# MJE13001_SWITCHING_NO_FEEDBACK.net
KiCad netlist of a schematic drawn in Altium Designer
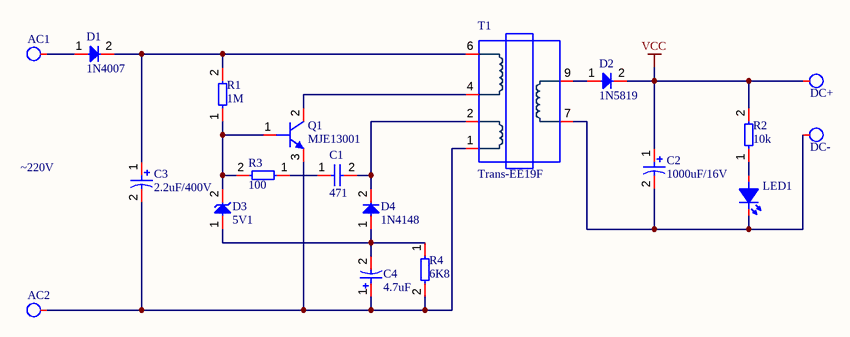
[diagram p0: MJE13001_SWITCHING_NO_FEEDBACK.SchDoc]

(export (version "E")
  (design (tool "Eeschema 10.0.6"))
  (components
    (comp (ref "AC1")
      (value "SolderPoint")
      (footprint "SolderPoint")
      (libsource (lib "Lib31082020") (part "SolderPoint"))
    )
    (comp (ref "AC2")
      (value "SolderPoint")
      (footprint "SolderPoint")
      (libsource (lib "Lib31082020") (part "SolderPoint"))
    )
    (comp (ref "C1")
      (value "471")
      (footprint "CAP_DISC_PITCH_2.54MM")
      (libsource (lib "Lib31082020") (part "Capacitors(Disc)"))
    )
    (comp (ref "C2")
      (value "1000uF/16V")
      (footprint "CAP_RAD_7mm")
      (libsource (lib "Lib31082020") (part "Capacitor(Radian)"))
    )
    (comp (ref "C3")
      (value "2.2uF/400V")
      (footprint "CAP_RAD_7mm")
      (libsource (lib "Lib31082020") (part "Capacitor(Radian)"))
    )
    (comp (ref "C4")
      (value "4.7uF")
      (footprint "CAP_RAD_4mm")
      (libsource (lib "Lib31082020") (part "Capacitor(Radian)"))
    )
    (comp (ref "D1") (value "1N4007") (footprint "DO-41") (libsource (lib "Lib31082020") (part "1N4007")))
    (comp (ref "D2")
      (value "1N5819")
      (footprint "DO-35 Horizontal")
      (libsource (lib "Lib31082020") (part "Diode 1N4148"))
    )
    (comp (ref "D3")
      (value "5V1")
      (footprint "DO-35 Horizontal")
      (libsource (lib "Lib31082020") (part "Diode Zener"))
    )
    (comp (ref "D4")
      (value "1N4148")
      (footprint "DO-35 Horizontal")
      (libsource (lib "Lib31082020") (part "Diode 1N4148"))
    )
    (comp (ref "DC+")
      (value "SolderPoint")
      (footprint "SolderPoint")
      (libsource (lib "Lib31082020") (part "SolderPoint"))
    )
    (comp (ref "DC-")
      (value "SolderPoint")
      (footprint "SolderPoint")
      (libsource (lib "Lib31082020") (part "SolderPoint"))
    )
    (comp (ref "LED1")
      (value "LED 5mm")
      (footprint "LED_5MM")
      (libsource (lib "Lib31082020") (part "LED 5mm"))
    )
    (comp (ref "Q1")
      (value "MJE13001")
      (footprint "TO-92")
      (libsource (lib "Lib31082020") (part "MJE13001_Type_F"))
    )
    (comp (ref "R1") (value "1M") (footprint "RES-0.25W-H-MF") (libsource (lib "") (part "Resistors THD_2")))
    (comp (ref "R2") (value "10k") (footprint "R0805") (libsource (lib "Lib31082020") (part "Resistor SMD")))
    (comp (ref "R3") (value "100") (footprint "RES-0.25W-H-MF") (libsource (lib "") (part "Resistors THD_1")))
    (comp (ref "R4")
      (value "6K8")
      (footprint "RES-0.25W-H-MF")
      (libsource (lib "Lib31082020") (part "Resistors THD"))
    )
    (comp (ref "T1")
      (value "Trans-EE19F")
      (footprint "TRANS_EE19F")
      (libsource (lib "Lib31082020") (part "Trans-EE19F"))
    )
  )
  (nets
    (net (code "1") (name "Net-(AC1-Pad1)") (class "Default")
      (node (ref "AC1") (pin "1") (pinfunction "1_1") (pintype "passive"))
      (node (ref "D1") (pin "1") (pinfunction "1_1") (pintype "passive"))
    )
    (net (code "2") (name "Net-(C1-Pad1)") (class "Default")
      (node (ref "C1") (pin "1") (pinfunction "1_1") (pintype "passive"))
      (node (ref "R3") (pin "1") (pinfunction "1_1") (pintype "passive"))
    )
    (net (code "3") (name "Net-(C1-Pad2)") (class "Default")
      (node (ref "C1") (pin "2") (pinfunction "2_2") (pintype "passive"))
      (node (ref "D4") (pin "2") (pinfunction "2_2") (pintype "passive"))
      (node (ref "T1") (pin "2") (pinfunction "2_2") (pintype "passive"))
    )
    (net (code "4") (name "Net-(C4-Pad2)") (class "Default")
      (node (ref "C4") (pin "2") (pinfunction "2_2") (pintype "passive"))
      (node (ref "D3") (pin "1") (pinfunction "1_1") (pintype "passive"))
      (node (ref "D4") (pin "1") (pinfunction "1_1") (pintype "passive"))
      (node (ref "R4") (pin "1") (pinfunction "1_1") (pintype "passive"))
    )
    (net (code "5") (name "Net-(D2-Pad1)") (class "Default")
      (node (ref "D2") (pin "1") (pinfunction "1_1") (pintype "passive"))
      (node (ref "T1") (pin "9") (pinfunction "9_9") (pintype "passive"))
    )
    (net (code "6") (name "Net-(LED1-A)") (class "Default")
      (node (ref "LED1") (pin "1") (pinfunction "A_1") (pintype "passive"))
      (node (ref "R2") (pin "1") (pinfunction "1_1") (pintype "passive"))
    )
    (net (code "7") (name "Net-(LED1-K)") (class "Default")
      (node (ref "C2") (pin "2") (pinfunction "2_2") (pintype "passive"))
      (node (ref "DC-") (pin "1") (pinfunction "1_1") (pintype "passive"))
      (node (ref "LED1") (pin "2") (pinfunction "K_2") (pintype "passive"))
      (node (ref "T1") (pin "7") (pinfunction "7_7") (pintype "passive"))
    )
    (net (code "8") (name "Net-(Q1-B)") (class "Default")
      (node (ref "D3") (pin "2") (pinfunction "2_2") (pintype "passive"))
      (node (ref "Q1") (pin "1") (pinfunction "B_1") (pintype "passive"))
      (node (ref "R1") (pin "1") (pinfunction "1_1") (pintype "passive"))
      (node (ref "R3") (pin "2") (pinfunction "2_2") (pintype "passive"))
    )
    (net (code "9") (name "Net-(Q1-C)") (class "Default")
      (node (ref "Q1") (pin "2") (pinfunction "C_2") (pintype "passive"))
      (node (ref "T1") (pin "4") (pinfunction "4_4") (pintype "passive"))
    )
    (net (code "10") (name "Net-(Q1-E)") (class "Default")
      (node (ref "AC2") (pin "1") (pinfunction "1_1") (pintype "passive"))
      (node (ref "C3") (pin "2") (pinfunction "2_2") (pintype "passive"))
      (node (ref "C4") (pin "1") (pinfunction "1_1") (pintype "passive"))
      (node (ref "Q1") (pin "3") (pinfunction "E_3") (pintype "passive"))
      (node (ref "R4") (pin "2") (pinfunction "2_2") (pintype "passive"))
      (node (ref "T1") (pin "1") (pinfunction "1_1") (pintype "passive"))
    )
    (net (code "11") (name "Net-(T1-61)") (class "Default")
      (node (ref "C3") (pin "1") (pinfunction "1_1") (pintype "passive"))
      (node (ref "D1") (pin "2") (pinfunction "2_2") (pintype "passive"))
      (node (ref "R1") (pin "2") (pinfunction "2_2") (pintype "passive"))
      (node (ref "T1") (pin "6") (pinfunction "61_6") (pintype "passive"))
    )
    (net (code "12") (name "VCC") (class "Default")
      (node (ref "C2") (pin "1") (pinfunction "1_1") (pintype "passive"))
      (node (ref "D2") (pin "2") (pinfunction "2_2") (pintype "passive"))
      (node (ref "DC+") (pin "1") (pinfunction "1_1") (pintype "passive"))
      (node (ref "R2") (pin "2") (pinfunction "2_2") (pintype "passive"))
    )
  )
)
